# PEAWS.net
KiCad netlist of a schematic drawn in EAGLE
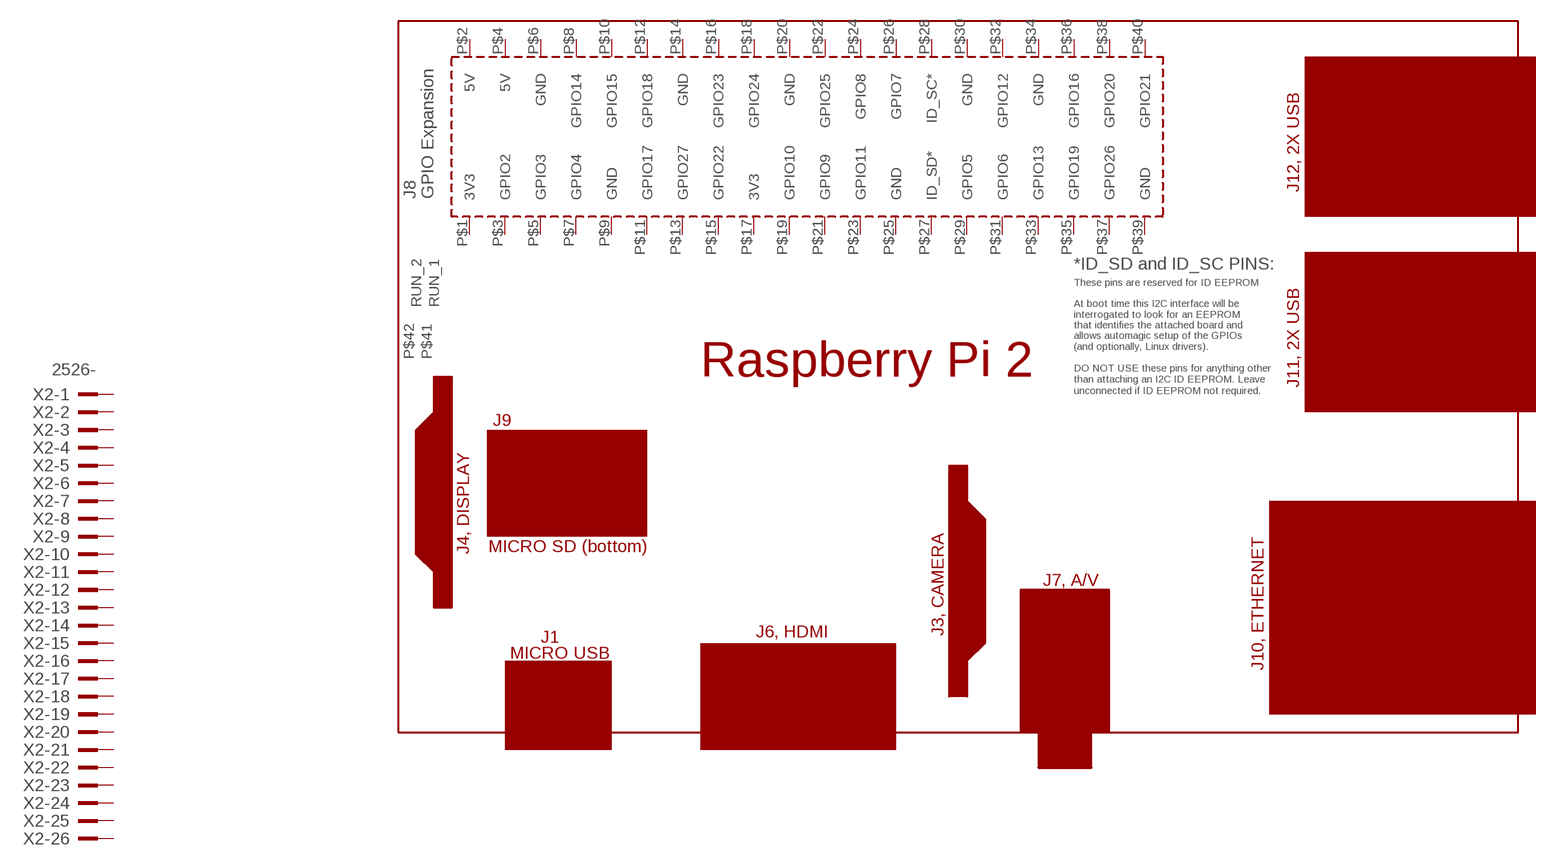
[diagram p0: schematic, sheet 1]
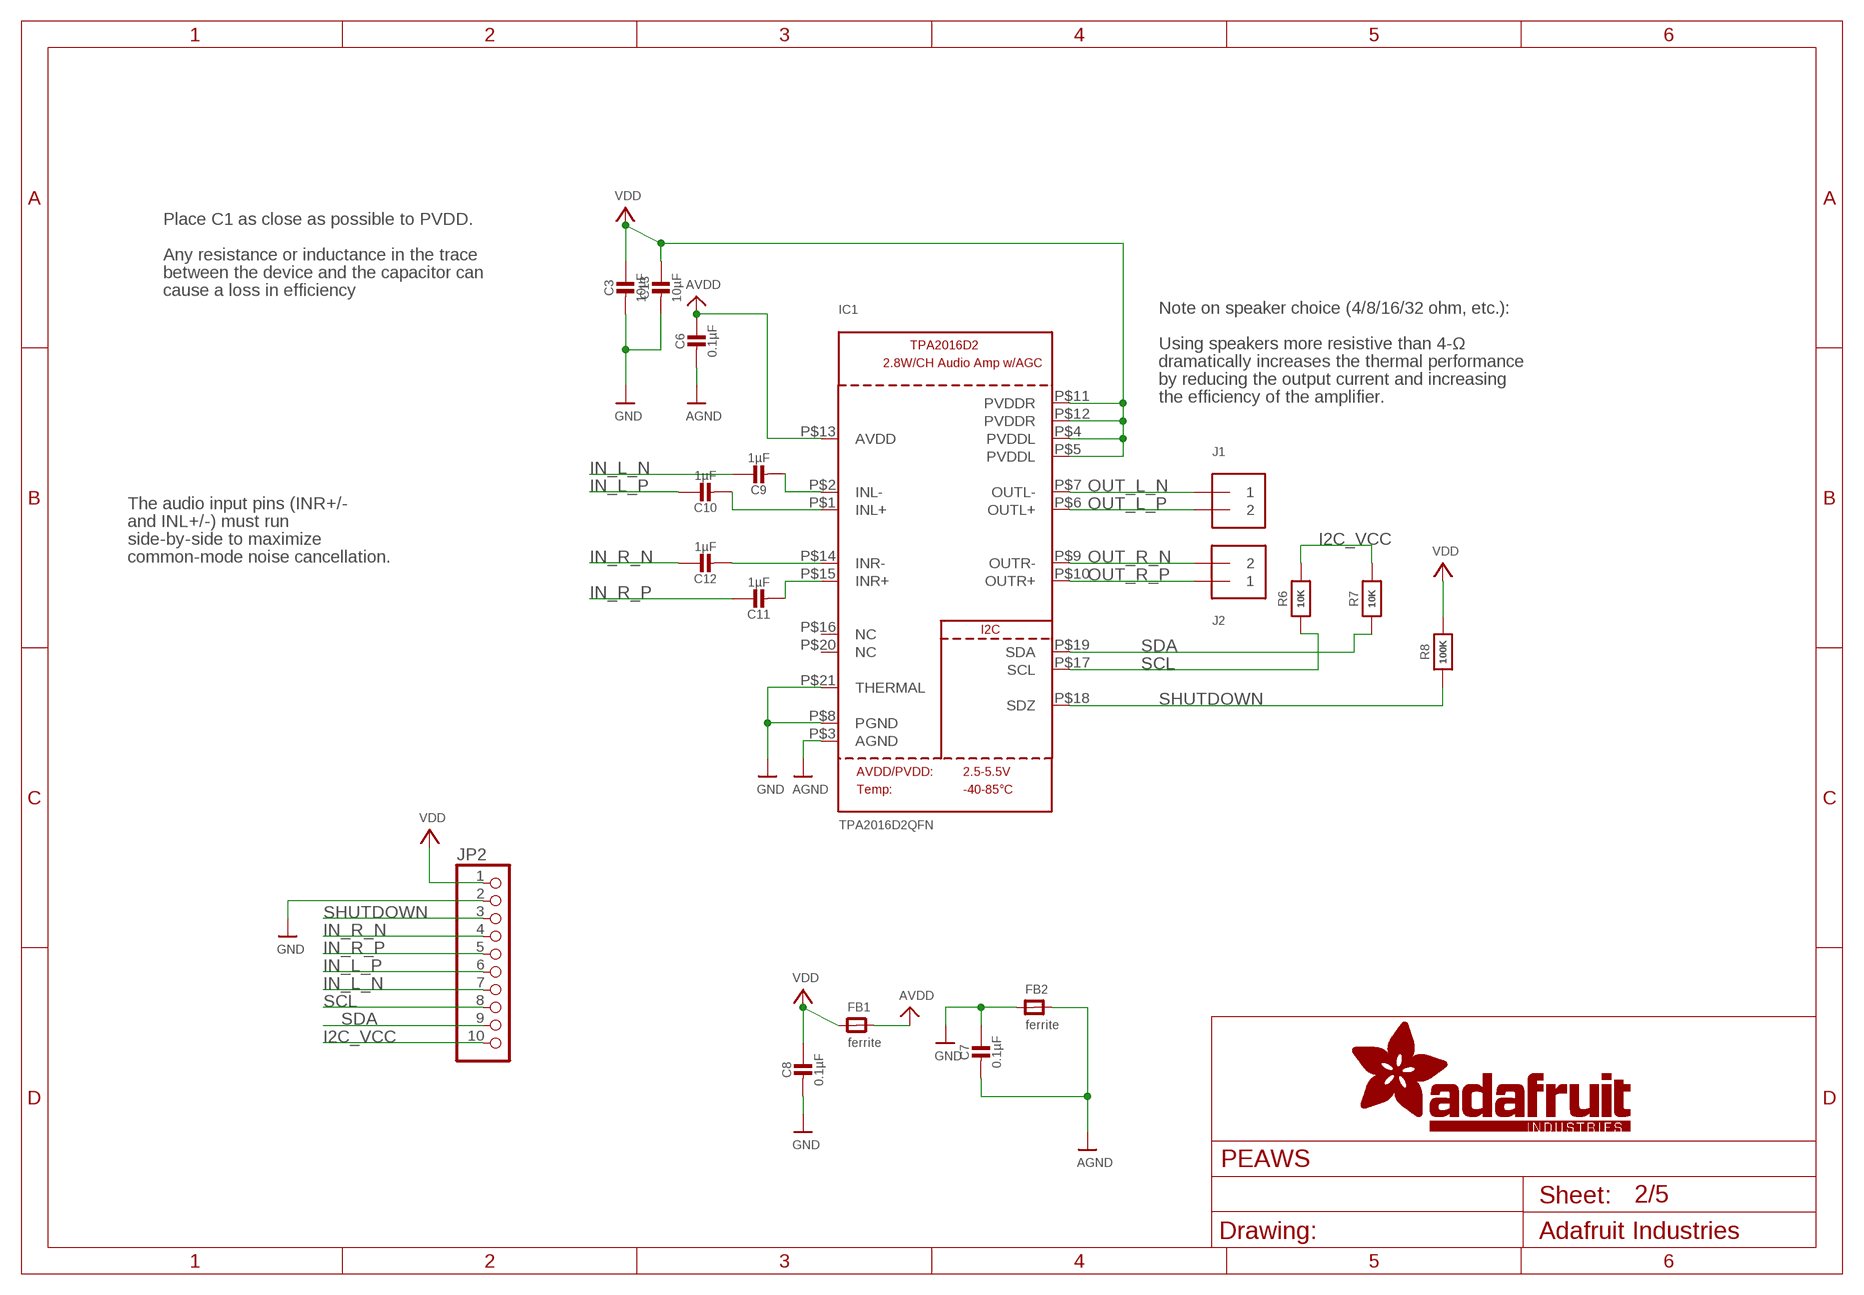
[diagram p1: schematic, sheet 2]
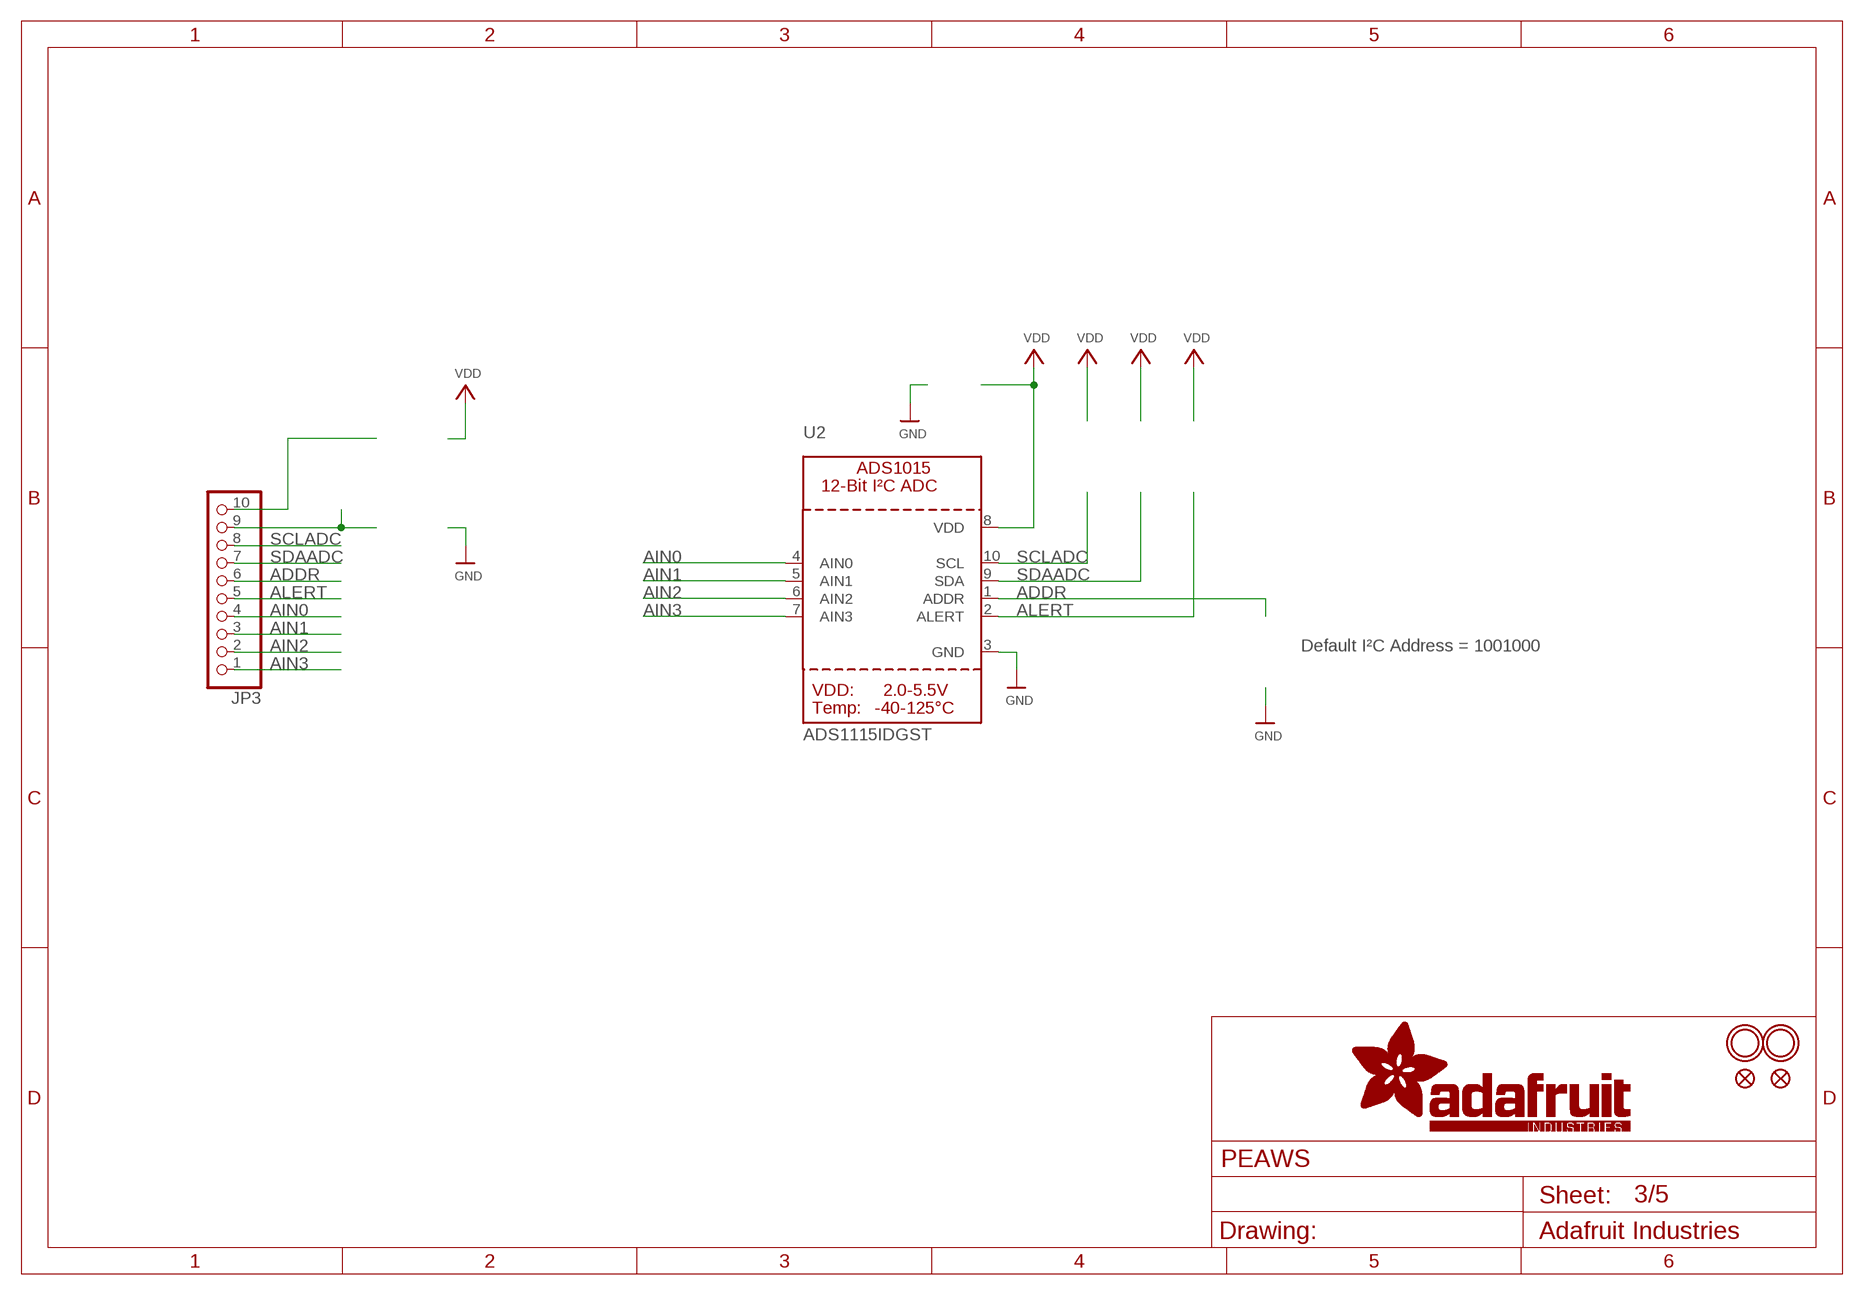
[diagram p2: schematic, sheet 3]
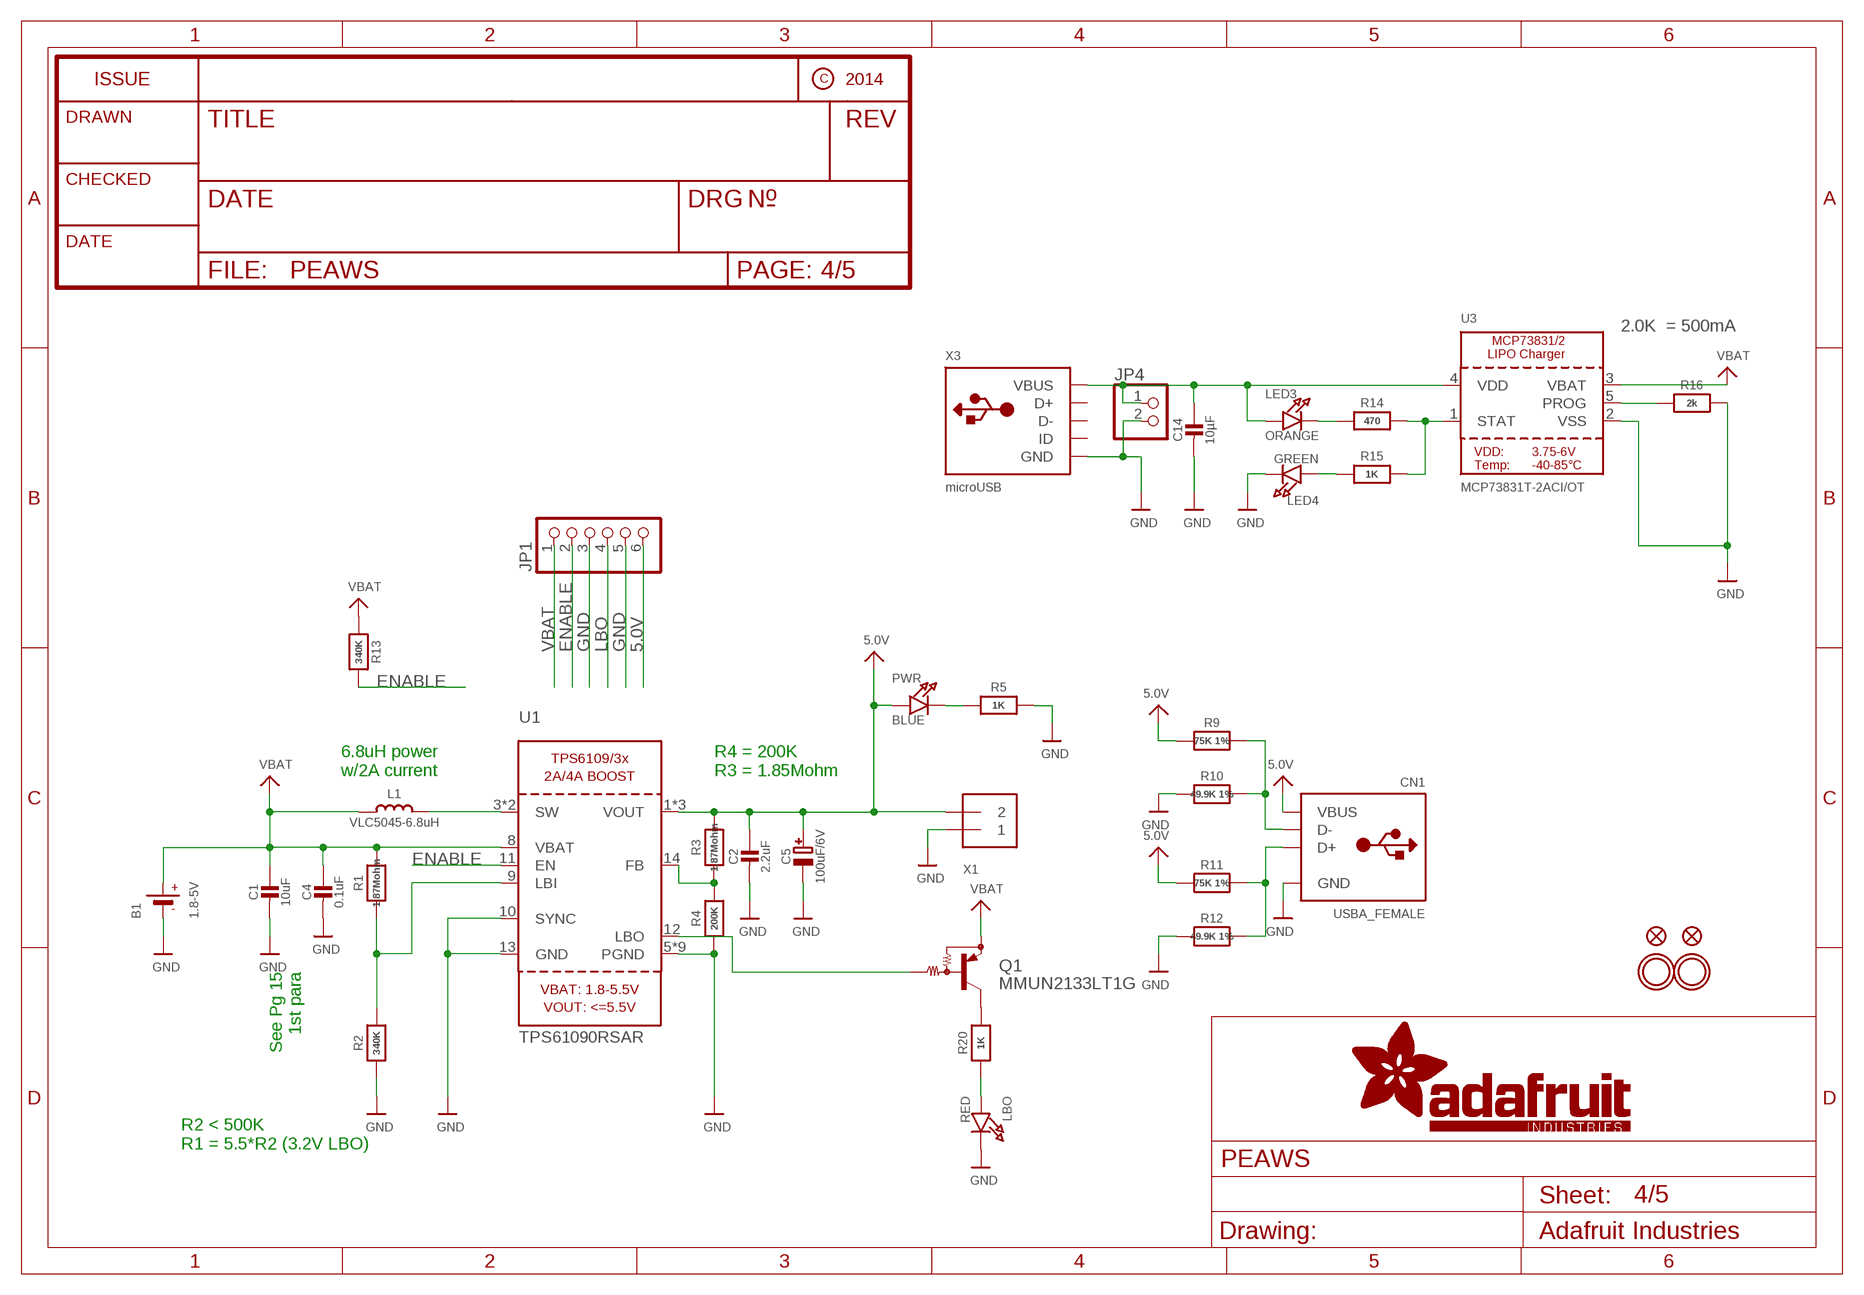
[diagram p3: schematic, sheet 4]
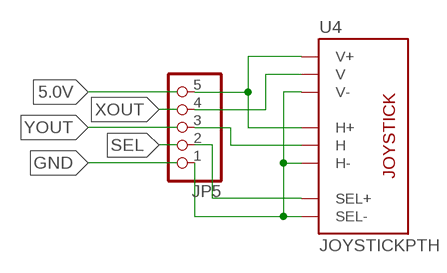
[diagram p4: schematic, sheet 5]

(export (version "E")
  (design (tool "Eeschema 10.0.6"))
  (components
    (comp (ref "C3")
      (value "10µF")
      (footprint "eagle-import:0805-NO")
      (libsource (lib "eagle-import") (part "CAP_CERAMIC0805-NOOUTLINE"))
    )
    (comp (ref "C6")
      (value "0.1µF")
      (footprint "eagle-import:0805-NO")
      (libsource (lib "eagle-import") (part "CAP_CERAMIC0805-NOOUTLINE"))
    )
    (comp (ref "C7")
      (value "0.1µF")
      (footprint "eagle-import:0805-NO")
      (libsource (lib "eagle-import") (part "CAP_CERAMIC0805-NOOUTLINE"))
    )
    (comp (ref "C8")
      (value "0.1µF")
      (footprint "eagle-import:0805-NO")
      (libsource (lib "eagle-import") (part "CAP_CERAMIC0805-NOOUTLINE"))
    )
    (comp (ref "C9")
      (value "1µF")
      (footprint "eagle-import:0805-NO")
      (libsource (lib "eagle-import") (part "CAP_CERAMIC0805-NOOUTLINE"))
    )
    (comp (ref "C10")
      (value "1µF")
      (footprint "eagle-import:0805-NO")
      (libsource (lib "eagle-import") (part "CAP_CERAMIC0805-NOOUTLINE"))
    )
    (comp (ref "C11")
      (value "1µF")
      (footprint "eagle-import:0805-NO")
      (libsource (lib "eagle-import") (part "CAP_CERAMIC0805-NOOUTLINE"))
    )
    (comp (ref "C12")
      (value "1µF")
      (footprint "eagle-import:0805-NO")
      (libsource (lib "eagle-import") (part "CAP_CERAMIC0805-NOOUTLINE"))
    )
    (comp (ref "C13")
      (value "10µF")
      (footprint "eagle-import:0805-NO")
      (libsource (lib "eagle-import") (part "CAP_CERAMIC0805-NOOUTLINE"))
    )
    (comp (ref "FB1")
      (value "ferrite")
      (footprint "eagle-import:_0805MP")
      (libsource (lib "eagle-import") (part "FERRITE_0805MP"))
    )
    (comp (ref "FB2")
      (value "ferrite")
      (footprint "eagle-import:_0805MP")
      (libsource (lib "eagle-import") (part "FERRITE_0805MP"))
    )
    (comp (ref "IC1")
      (value "TPA2016D2QFN")
      (footprint "eagle-import:QFN20_4MM")
      (libsource (lib "eagle-import") (part "TPA2016D2QFN"))
    )
    (comp (ref "J1")
      (value "TERMBLOCK_1X2")
      (footprint "eagle-import:TERMBLOCK_1X2-3.5MM")
      (libsource (lib "eagle-import") (part "TERMBLOCK_1X2"))
    )
    (comp (ref "J2")
      (value "TERMBLOCK_1X2")
      (footprint "eagle-import:TERMBLOCK_1X2-3.5MM")
      (libsource (lib "eagle-import") (part "TERMBLOCK_1X2"))
    )
    (comp (ref "JP2")
      (value "HEADER-1X1070MIL")
      (footprint "eagle-import:1X10_ROUND70")
      (libsource (lib "eagle-import") (part "HEADER-1X1070MIL"))
    )
    (comp (ref "R6")
      (value "10K")
      (footprint "eagle-import:0805-NO")
      (libsource (lib "eagle-import") (part "RESISTOR0805_NOOUTLINE"))
    )
    (comp (ref "R7")
      (value "10K")
      (footprint "eagle-import:0805-NO")
      (libsource (lib "eagle-import") (part "RESISTOR0805_NOOUTLINE"))
    )
    (comp (ref "R8")
      (value "100K")
      (footprint "eagle-import:0805-NO")
      (libsource (lib "eagle-import") (part "RESISTOR0805_NOOUTLINE"))
    )
    (comp (ref "PCB1")
      (value "RPI2")
      (footprint "eagle-import:RPI2")
      (libsource (lib "eagle-import") (part "RPI2"))
    )
    (comp (ref "X2")
      (value "2526-")
      (footprint "eagle-import:PAK100_2500-26")
      (libsource (lib "eagle-import") (part "2526-"))
    )
    (comp (ref "JP5")
      (value "PINHD-1X5")
      (footprint "eagle-import:1X05")
      (libsource (lib "eagle-import") (part "PINHD-1X5"))
    )
    (comp (ref "U4")
      (value "JOYSTICKPTH")
      (footprint "eagle-import:JOYSTICK")
      (libsource (lib "eagle-import") (part "JOYSTICKPTH"))
    )
    (comp (ref "FID1")
      (value "FIDUCIAL\"\"")
      (footprint "eagle-import:FIDUCIAL_1MM")
      (libsource (lib "eagle-import") (part "FIDUCIAL{dblquote}{dblquote}"))
    )
    (comp (ref "FID2")
      (value "FIDUCIAL\"\"")
      (footprint "eagle-import:FIDUCIAL_1MM")
      (libsource (lib "eagle-import") (part "FIDUCIAL{dblquote}{dblquote}"))
    )
    (comp (ref "JP3")
      (value "HEADER-1X1070MIL")
      (footprint "eagle-import:1X10_ROUND70")
      (libsource (lib "eagle-import") (part "HEADER-1X1070MIL"))
    )
    (comp (ref "U$55")
      (value "MOUNTINGHOLE2.5")
      (footprint "eagle-import:MOUNTINGHOLE_2.5_PLATED")
      (libsource (lib "eagle-import") (part "MOUNTINGHOLE2.5"))
    )
    (comp (ref "U$56")
      (value "MOUNTINGHOLE2.5")
      (footprint "eagle-import:MOUNTINGHOLE_2.5_PLATED")
      (libsource (lib "eagle-import") (part "MOUNTINGHOLE2.5"))
    )
    (comp (ref "U2")
      (value "ADS1115IDGST")
      (footprint "eagle-import:MSOP10")
      (libsource (lib "eagle-import") (part "ADC_ADS1015"))
    )
    (comp (ref "B1")
      (value "1.8-5V")
      (footprint "eagle-import:JSTPH2")
      (libsource (lib "eagle-import") (part "BATTERY"))
    )
    (comp (ref "C1")
      (value "10uF")
      (footprint "eagle-import:0805-NO")
      (libsource (lib "eagle-import") (part "CAP_CERAMIC0805-NOOUTLINE"))
    )
    (comp (ref "C2")
      (value "2.2uF")
      (footprint "eagle-import:0805-NO")
      (libsource (lib "eagle-import") (part "CAP_CERAMIC0805-NOOUTLINE"))
    )
    (comp (ref "C4")
      (value "0.1uF")
      (footprint "eagle-import:0805-NO")
      (libsource (lib "eagle-import") (part "CAP_CERAMIC0805-NOOUTLINE"))
    )
    (comp (ref "C5")
      (value "100uF/6V")
      (footprint "eagle-import:EIA3528-21_B-R")
      (libsource (lib "eagle-import") (part "CAP_TANTALUMB/3528_REFLOW"))
    )
    (comp (ref "C14")
      (value "10µF")
      (footprint "eagle-import:0805-NO")
      (libsource (lib "eagle-import") (part "CAP_CERAMIC0805-NOOUTLINE"))
    )
    (comp (ref "CN1")
      (value "USBA_FEMALE")
      (footprint "eagle-import:USB_HOST-PTH")
      (libsource (lib "eagle-import") (part "USB_TYPEAPTHFML"))
    )
    (comp (ref "FID3")
      (value "FIDUCIAL\"\"")
      (footprint "eagle-import:FIDUCIAL_1MM")
      (libsource (lib "eagle-import") (part "FIDUCIAL{dblquote}{dblquote}"))
    )
    (comp (ref "FID4")
      (value "FIDUCIAL\"\"")
      (footprint "eagle-import:FIDUCIAL_1MM")
      (fields (field (name "BOM") "EXCLUDE"))
      (libsource (lib "eagle-import") (part "FIDUCIAL{dblquote}{dblquote}"))
    )
    (comp (ref "JP1")
      (value "PINHD-1X6CB")
      (footprint "eagle-import:1X06-CLEANBIG")
      (libsource (lib "eagle-import") (part "PINHD-1X6CB"))
    )
    (comp (ref "JP4")
      (value "HEADER-1X2ROUND")
      (footprint "eagle-import:1X02_ROUND")
      (libsource (lib "eagle-import") (part "HEADER-1X2ROUND"))
    )
    (comp (ref "L1")
      (value "VLC5045-6.8uH")
      (footprint "eagle-import:INDUCTOR_5X5MM_TDK_VLC5045")
      (libsource (lib "eagle-import") (part "INDUCTORTDK_VLC5045"))
    )
    (comp (ref "LBO")
      (value "RED")
      (footprint "eagle-import:CHIPLED_0805_NOOUTLINE")
      (libsource (lib "eagle-import") (part "LED0805_NOOUTLINE"))
    )
    (comp (ref "LED3")
      (value "ORANGE")
      (footprint "eagle-import:CHIPLED_0805_NOOUTLINE")
      (libsource (lib "eagle-import") (part "LED0805_NOOUTLINE"))
    )
    (comp (ref "LED4")
      (value "GREEN")
      (footprint "eagle-import:CHIPLED_0805_NOOUTLINE")
      (libsource (lib "eagle-import") (part "LED0805_NOOUTLINE"))
    )
    (comp (ref "PWR")
      (value "BLUE")
      (footprint "eagle-import:CHIPLED_0805_NOOUTLINE")
      (libsource (lib "eagle-import") (part "LED0805_NOOUTLINE"))
    )
    (comp (ref "Q1")
      (value "MMUN2133LT1G")
      (footprint "eagle-import:SC59-BEC")
      (libsource (lib "eagle-import") (part "-PNP_DRIVER-SC59-BECMUN2114T1"))
    )
    (comp (ref "R1")
      (value "1.87Mohm")
      (footprint "eagle-import:0805-NO")
      (libsource (lib "eagle-import") (part "RESISTOR0805_NOOUTLINE"))
    )
    (comp (ref "R2")
      (value "340K")
      (footprint "eagle-import:0805-NO")
      (libsource (lib "eagle-import") (part "RESISTOR0805_NOOUTLINE"))
    )
    (comp (ref "R3")
      (value "1.87Mohm")
      (footprint "eagle-import:0805-NO")
      (libsource (lib "eagle-import") (part "RESISTOR0805_NOOUTLINE"))
    )
    (comp (ref "R4")
      (value "200K")
      (footprint "eagle-import:0805-NO")
      (libsource (lib "eagle-import") (part "RESISTOR0805_NOOUTLINE"))
    )
    (comp (ref "R5")
      (value "1K")
      (footprint "eagle-import:0805-NO")
      (libsource (lib "eagle-import") (part "RESISTOR0805_NOOUTLINE"))
    )
    (comp (ref "R9")
      (value "75K 1%")
      (footprint "eagle-import:0805-NO")
      (libsource (lib "eagle-import") (part "RESISTOR0805_NOOUTLINE"))
    )
    (comp (ref "R10")
      (value "49.9K 1%")
      (footprint "eagle-import:0805-NO")
      (libsource (lib "eagle-import") (part "RESISTOR0805_NOOUTLINE"))
    )
    (comp (ref "R11")
      (value "75K 1%")
      (footprint "eagle-import:0805-NO")
      (libsource (lib "eagle-import") (part "RESISTOR0805_NOOUTLINE"))
    )
    (comp (ref "R12")
      (value "49.9K 1%")
      (footprint "eagle-import:0805-NO")
      (libsource (lib "eagle-import") (part "RESISTOR0805_NOOUTLINE"))
    )
    (comp (ref "R13")
      (value "340K")
      (footprint "eagle-import:0805-NO")
      (libsource (lib "eagle-import") (part "RESISTOR0805_NOOUTLINE"))
    )
    (comp (ref "R14")
      (value "470")
      (footprint "eagle-import:0805-NO")
      (libsource (lib "eagle-import") (part "RESISTOR0805_NOOUTLINE"))
    )
    (comp (ref "R15")
      (value "1K")
      (footprint "eagle-import:0805-NO")
      (libsource (lib "eagle-import") (part "RESISTOR0805_NOOUTLINE"))
    )
    (comp (ref "R16")
      (value "2k")
      (footprint "eagle-import:0805-NO")
      (libsource (lib "eagle-import") (part "RESISTOR0805_NOOUTLINE"))
    )
    (comp (ref "R20")
      (value "1K")
      (footprint "eagle-import:0805-NO")
      (libsource (lib "eagle-import") (part "RESISTOR0805_NOOUTLINE"))
    )
    (comp (ref "U$3")
      (value "MOUNTINGHOLE2.5")
      (footprint "eagle-import:MOUNTINGHOLE_2.5_PLATED")
      (libsource (lib "eagle-import") (part "MOUNTINGHOLE2.5"))
    )
    (comp (ref "U$6")
      (value "MOUNTINGHOLE2.5")
      (footprint "eagle-import:MOUNTINGHOLE_2.5_PLATED")
      (libsource (lib "eagle-import") (part "MOUNTINGHOLE2.5"))
    )
    (comp (ref "U1")
      (value "TPS61090RSAR")
      (footprint "eagle-import:PVQFN-16")
      (libsource (lib "eagle-import") (part "VREG_TPS6103X"))
    )
    (comp (ref "U3")
      (value "MCP73831T-2ACI/OT")
      (footprint "eagle-import:SOT23-5")
      (libsource (lib "eagle-import") (part "MCP73831/2"))
    )
    (comp (ref "X1")
      (value "TERMBLOCK_1X2")
      (footprint "eagle-import:TERMBLOCK_1X2-3.5MM")
      (libsource (lib "eagle-import") (part "TERMBLOCK_1X2"))
    )
    (comp (ref "X3")
      (value "microUSB")
      (footprint "eagle-import:4UCONN_20329")
      (libsource (lib "eagle-import") (part "USBMICRO_20329"))
    )
  )
  (nets
    (net (code "1") (name "5.0V") (class "Default")
      (node (ref "C2") (pin "1") (pinfunction "1_1") (pintype "passive"))
      (node (ref "C5") (pin "+") (pinfunction "+_+") (pintype "passive"))
      (node (ref "CN1") (pin "VBUS") (pinfunction "VBUS_VBUS") (pintype "power_in"))
      (node (ref "JP1") (pin "6") (pinfunction "6_6") (pintype "passive"))
      (node (ref "PWR") (pin "A") (pinfunction "A_A") (pintype "passive"))
      (node (ref "R11") (pin "2") (pinfunction "2_2") (pintype "passive"))
      (node (ref "R3") (pin "2") (pinfunction "2_2") (pintype "passive"))
      (node (ref "R9") (pin "2") (pinfunction "2_2") (pintype "passive"))
      (node (ref "U1") (pin "1") (pinfunction "VOUT_1") (pintype "power_in"))
      (node (ref "U1") (pin "15") (pinfunction "VOUT_15") (pintype "power_in"))
      (node (ref "U1") (pin "16") (pinfunction "VOUT_16") (pintype "power_in"))
      (node (ref "X1") (pin "2") (pinfunction "2_2") (pintype "passive"))
    )
    (net (code "2") (name "ADDR") (class "Default")
      (node (ref "JP3") (pin "6") (pinfunction "6_6") (pintype "passive"))
      (node (ref "U2") (pin "1") (pinfunction "ADDR_1") (pintype "bidirectional"))
    )
    (net (code "3") (name "AGND") (class "Default")
      (node (ref "C6") (pin "2") (pinfunction "2_2") (pintype "passive"))
      (node (ref "C7") (pin "2") (pinfunction "2_2") (pintype "passive"))
      (node (ref "FB2") (pin "2") (pinfunction "P$2_2") (pintype "passive"))
      (node (ref "IC1") (pin "P$3") (pinfunction "AGND_P$3") (pintype "power_in"))
    )
    (net (code "4") (name "AIN0") (class "Default")
      (node (ref "JP3") (pin "4") (pinfunction "4_4") (pintype "passive"))
      (node (ref "U2") (pin "4") (pinfunction "AIN0_4") (pintype "bidirectional"))
    )
    (net (code "5") (name "AIN1") (class "Default")
      (node (ref "JP3") (pin "3") (pinfunction "3_3") (pintype "passive"))
      (node (ref "U2") (pin "5") (pinfunction "AIN1_5") (pintype "bidirectional"))
    )
    (net (code "6") (name "AIN2") (class "Default")
      (node (ref "JP3") (pin "2") (pinfunction "2_2") (pintype "passive"))
      (node (ref "U2") (pin "6") (pinfunction "AIN2_6") (pintype "bidirectional"))
    )
    (net (code "7") (name "AIN3") (class "Default")
      (node (ref "JP3") (pin "1") (pinfunction "1_1") (pintype "passive"))
      (node (ref "U2") (pin "7") (pinfunction "AIN3_7") (pintype "bidirectional"))
    )
    (net (code "8") (name "ALERT") (class "Default")
      (node (ref "JP3") (pin "5") (pinfunction "5_5") (pintype "passive"))
      (node (ref "U2") (pin "2") (pinfunction "ALERT_2") (pintype "bidirectional"))
    )
    (net (code "9") (name "AVDD") (class "Default")
      (node (ref "C6") (pin "1") (pinfunction "1_1") (pintype "passive"))
      (node (ref "FB1") (pin "2") (pinfunction "P$2_2") (pintype "passive"))
      (node (ref "IC1") (pin "P$13") (pinfunction "AVDD_P$13") (pintype "power_in"))
    )
    (net (code "10") (name "ENABLE") (class "Default")
      (node (ref "JP1") (pin "2") (pinfunction "2_2") (pintype "passive"))
      (node (ref "R13") (pin "2") (pinfunction "2_2") (pintype "passive"))
      (node (ref "U1") (pin "11") (pinfunction "EN_11") (pintype "input"))
    )
    (net (code "11") (name "GND") (class "Default")
      (node (ref "B1") (pin "1") (pinfunction "-_1") (pintype "passive"))
      (node (ref "C1") (pin "2") (pinfunction "2_2") (pintype "passive"))
      (node (ref "C13") (pin "2") (pinfunction "2_2") (pintype "passive"))
      (node (ref "C14") (pin "2") (pinfunction "2_2") (pintype "passive"))
      (node (ref "C2") (pin "2") (pinfunction "2_2") (pintype "passive"))
      (node (ref "C3") (pin "2") (pinfunction "2_2") (pintype "passive"))
      (node (ref "C4") (pin "2") (pinfunction "2_2") (pintype "passive"))
      (node (ref "C5") (pin "-") (pinfunction "-_-") (pintype "passive"))
      (node (ref "C7") (pin "1") (pinfunction "1_1") (pintype "passive"))
      (node (ref "C8") (pin "2") (pinfunction "2_2") (pintype "passive"))
      (node (ref "CN1") (pin "GND") (pinfunction "GND_GND") (pintype "power_in"))
      (node (ref "FB2") (pin "1") (pinfunction "P$1_1") (pintype "passive"))
      (node (ref "IC1") (pin "P$21") (pinfunction "THERMAL_P$21") (pintype "bidirectional"))
      (node (ref "IC1") (pin "P$8") (pinfunction "PGND_P$8") (pintype "power_in"))
      (node (ref "JP1") (pin "3") (pinfunction "3_3") (pintype "passive"))
      (node (ref "JP1") (pin "5") (pinfunction "5_5") (pintype "passive"))
      (node (ref "JP2") (pin "2") (pinfunction "2_2") (pintype "passive"))
      (node (ref "JP4") (pin "2") (pinfunction "2_2") (pintype "passive"))
      (node (ref "LBO") (pin "C") (pinfunction "C_C") (pintype "passive"))
      (node (ref "LED4") (pin "C") (pinfunction "C_C") (pintype "passive"))
      (node (ref "R10") (pin "2") (pinfunction "2_2") (pintype "passive"))
      (node (ref "R12") (pin "2") (pinfunction "2_2") (pintype "passive"))
      (node (ref "R16") (pin "2") (pinfunction "2_2") (pintype "passive"))
      (node (ref "R2") (pin "1") (pinfunction "1_1") (pintype "passive"))
      (node (ref "R4") (pin "1") (pinfunction "1_1") (pintype "passive"))
      (node (ref "R5") (pin "2") (pinfunction "2_2") (pintype "passive"))
      (node (ref "U1") (pin "10") (pinfunction "SYNC_10") (pintype "input"))
      (node (ref "U1") (pin "13") (pinfunction "GND_13") (pintype "power_in"))
      (node (ref "U1") (pin "5") (pinfunction "PGND_5") (pintype "power_in"))
      (node (ref "U1") (pin "6") (pinfunction "PGND_6") (pintype "power_in"))
      (node (ref "U1") (pin "7") (pinfunction "PGND_7") (pintype "power_in"))
      (node (ref "U1") (pin "P$18") (pinfunction "PGND_P$18") (pintype "power_in"))
      (node (ref "U1") (pin "P$19") (pinfunction "PGND_P$19") (pintype "power_in"))
      (node (ref "U1") (pin "P$20") (pinfunction "PGND_P$20") (pintype "power_in"))
      (node (ref "U1") (pin "P$21") (pinfunction "PGND_P$21") (pintype "power_in"))
      (node (ref "U1") (pin "P$22") (pinfunction "PGND_P$22") (pintype "power_in"))
      (node (ref "U1") (pin "THERMAL") (pinfunction "PGND_THERMAL") (pintype "power_in"))
      (node (ref "U2") (pin "3") (pinfunction "GND_3") (pintype "bidirectional"))
      (node (ref "U3") (pin "2") (pinfunction "VSS_2") (pintype "power_in"))
      (node (ref "X1") (pin "1") (pinfunction "1_1") (pintype "passive"))
      (node (ref "X3") (pin "BASE@1") (pinfunction "GND_BASE@1") (pintype "power_in"))
      (node (ref "X3") (pin "BASE@2") (pinfunction "GND_BASE@2") (pintype "power_in"))
      (node (ref "X3") (pin "GND") (pinfunction "GND_GND") (pintype "power_in"))
      (node (ref "X3") (pin "SPRT@1") (pinfunction "GND_SPRT@1") (pintype "power_in"))
      (node (ref "X3") (pin "SPRT@2") (pinfunction "GND_SPRT@2") (pintype "power_in"))
      (node (ref "X3") (pin "SPRT@3") (pinfunction "GND_SPRT@3") (pintype "power_in"))
      (node (ref "X3") (pin "SPRT@4") (pinfunction "GND_SPRT@4") (pintype "power_in"))
    )
    (net (code "12") (name "I2C_VCC") (class "Default")
      (node (ref "JP2") (pin "10") (pinfunction "10_10") (pintype "passive"))
      (node (ref "R6") (pin "2") (pinfunction "2_2") (pintype "passive"))
      (node (ref "R7") (pin "2") (pinfunction "2_2") (pintype "passive"))
    )
    (net (code "13") (name "IN_L_N") (class "Default")
      (node (ref "C9") (pin "1") (pinfunction "1_1") (pintype "passive"))
      (node (ref "JP2") (pin "7") (pinfunction "7_7") (pintype "passive"))
    )
    (net (code "14") (name "IN_L_P") (class "Default")
      (node (ref "C10") (pin "1") (pinfunction "1_1") (pintype "passive"))
      (node (ref "JP2") (pin "6") (pinfunction "6_6") (pintype "passive"))
    )
    (net (code "15") (name "IN_R_N") (class "Default")
      (node (ref "C12") (pin "1") (pinfunction "1_1") (pintype "passive"))
      (node (ref "JP2") (pin "4") (pinfunction "4_4") (pintype "passive"))
    )
    (net (code "16") (name "IN_R_P") (class "Default")
      (node (ref "C11") (pin "1") (pinfunction "1_1") (pintype "passive"))
      (node (ref "JP2") (pin "5") (pinfunction "5_5") (pintype "passive"))
    )
    (net (code "17") (name "LBO") (class "Default")
      (node (ref "JP1") (pin "4") (pinfunction "4_4") (pintype "passive"))
      (node (ref "Q1") (pin "B") (pinfunction "B_B") (pintype "passive"))
      (node (ref "U1") (pin "12") (pinfunction "LBO_12") (pintype "output"))
    )
    (net (code "18") (name "Net-(CN1-PadD+)") (class "Default")
      (node (ref "CN1") (pin "D+") (pinfunction "D+_D+") (pintype "bidirectional"))
      (node (ref "R11") (pin "1") (pinfunction "1_1") (pintype "passive"))
      (node (ref "R12") (pin "1") (pinfunction "1_1") (pintype "passive"))
    )
    (net (code "19") (name "Net-(CN1-PadD-)") (class "Default")
      (node (ref "CN1") (pin "D-") (pinfunction "D-_D-") (pintype "bidirectional"))
      (node (ref "R10") (pin "1") (pinfunction "1_1") (pintype "passive"))
      (node (ref "R9") (pin "1") (pinfunction "1_1") (pintype "passive"))
    )
    (net (code "20") (name "Net-(IC1-INL+)") (class "Default")
      (node (ref "C10") (pin "2") (pinfunction "2_2") (pintype "passive"))
      (node (ref "IC1") (pin "P$1") (pinfunction "INL+_P$1") (pintype "input"))
    )
    (net (code "21") (name "Net-(IC1-INL-)") (class "Default")
      (node (ref "C9") (pin "2") (pinfunction "2_2") (pintype "passive"))
      (node (ref "IC1") (pin "P$2") (pinfunction "INL-_P$2") (pintype "input"))
    )
    (net (code "22") (name "Net-(IC1-INR+)") (class "Default")
      (node (ref "C11") (pin "2") (pinfunction "2_2") (pintype "passive"))
      (node (ref "IC1") (pin "P$15") (pinfunction "INR+_P$15") (pintype "input"))
    )
    (net (code "23") (name "Net-(IC1-INR-)") (class "Default")
      (node (ref "C12") (pin "2") (pinfunction "2_2") (pintype "passive"))
      (node (ref "IC1") (pin "P$14") (pinfunction "INR-_P$14") (pintype "input"))
    )
    (net (code "24") (name "Net-(L1-2)") (class "Default")
      (node (ref "L1") (pin "P$2") (pinfunction "2_P$2") (pintype "passive"))
      (node (ref "U1") (pin "3") (pinfunction "SW_3") (pintype "input"))
      (node (ref "U1") (pin "4") (pinfunction "SW_4") (pintype "input"))
    )
    (net (code "25") (name "Net-(LBO-PadA)") (class "Default")
      (node (ref "LBO") (pin "A") (pinfunction "A_A") (pintype "passive"))
      (node (ref "R20") (pin "1") (pinfunction "1_1") (pintype "passive"))
    )
    (net (code "26") (name "Net-(LED3-PadC)") (class "Default")
      (node (ref "LED3") (pin "C") (pinfunction "C_C") (pintype "passive"))
      (node (ref "R14") (pin "1") (pinfunction "1_1") (pintype "passive"))
    )
    (net (code "27") (name "Net-(LED4-PadA)") (class "Default")
      (node (ref "LED4") (pin "A") (pinfunction "A_A") (pintype "passive"))
      (node (ref "R15") (pin "1") (pinfunction "1_1") (pintype "passive"))
    )
    (net (code "28") (name "Net-(PWR-PadC)") (class "Default")
      (node (ref "PWR") (pin "C") (pinfunction "C_C") (pintype "passive"))
      (node (ref "R5") (pin "1") (pinfunction "1_1") (pintype "passive"))
    )
    (net (code "29") (name "Net-(Q1-PadC)") (class "Default")
      (node (ref "Q1") (pin "C") (pinfunction "C_C") (pintype "passive"))
      (node (ref "R20") (pin "2") (pinfunction "2_2") (pintype "passive"))
    )
    (net (code "30") (name "Net-(U1-FB)") (class "Default")
      (node (ref "R3") (pin "1") (pinfunction "1_1") (pintype "passive"))
      (node (ref "R4") (pin "2") (pinfunction "2_2") (pintype "passive"))
      (node (ref "U1") (pin "14") (pinfunction "FB_14") (pintype "input"))
    )
    (net (code "31") (name "Net-(U1-LBI)") (class "Default")
      (node (ref "R1") (pin "1") (pinfunction "1_1") (pintype "passive"))
      (node (ref "R2") (pin "2") (pinfunction "2_2") (pintype "passive"))
      (node (ref "U1") (pin "9") (pinfunction "LBI_9") (pintype "input"))
    )
    (net (code "32") (name "Net-(U3-PROG)") (class "Default")
      (node (ref "R16") (pin "1") (pinfunction "1_1") (pintype "passive"))
      (node (ref "U3") (pin "5") (pinfunction "PROG_5") (pintype "input"))
    )
    (net (code "33") (name "Net-(U3-STAT)") (class "Default")
      (node (ref "R14") (pin "2") (pinfunction "2_2") (pintype "passive"))
      (node (ref "R15") (pin "2") (pinfunction "2_2") (pintype "passive"))
      (node (ref "U3") (pin "1") (pinfunction "STAT_1") (pintype "output"))
    )
    (net (code "34") (name "Net-(U3-VDD)") (class "Default")
      (node (ref "C14") (pin "1") (pinfunction "1_1") (pintype "passive"))
      (node (ref "JP4") (pin "1") (pinfunction "1_1") (pintype "passive"))
      (node (ref "LED3") (pin "A") (pinfunction "A_A") (pintype "passive"))
      (node (ref "U3") (pin "4") (pinfunction "VDD_4") (pintype "power_in"))
      (node (ref "X3") (pin "VBUS") (pinfunction "VBUS_VBUS") (pintype "power_in"))
    )
    (net (code "35") (name "Net-(U4-H)") (class "Default")
      (node (ref "JP5") (pin "3") (pinfunction "3_3") (pintype "passive"))
      (node (ref "U4") (pin "H2") (pinfunction "H_H2") (pintype "bidirectional"))
    )
    (net (code "36") (name "Net-(U4-H+)") (class "Default")
      (node (ref "JP5") (pin "5") (pinfunction "5_5") (pintype "passive"))
      (node (ref "U4") (pin "H1") (pinfunction "H+_H1") (pintype "bidirectional"))
      (node (ref "U4") (pin "V1") (pinfunction "V+_V1") (pintype "bidirectional"))
    )
    (net (code "37") (name "Net-(U4-H-)") (class "Default")
      (node (ref "JP5") (pin "1") (pinfunction "1_1") (pintype "passive"))
      (node (ref "U4") (pin "B2A") (pinfunction "SEL-_B2A") (pintype "bidirectional"))
      (node (ref "U4") (pin "H3") (pinfunction "H-_H3") (pintype "bidirectional"))
      (node (ref "U4") (pin "V3") (pinfunction "V-_V3") (pintype "bidirectional"))
    )
    (net (code "38") (name "Net-(U4-SEL+)") (class "Default")
      (node (ref "JP5") (pin "2") (pinfunction "2_2") (pintype "passive"))
      (node (ref "U4") (pin "B1A") (pinfunction "SEL+_B1A") (pintype "bidirectional"))
    )
    (net (code "39") (name "Net-(U4-V)") (class "Default")
      (node (ref "JP5") (pin "4") (pinfunction "4_4") (pintype "passive"))
      (node (ref "U4") (pin "V2") (pinfunction "V_V2") (pintype "bidirectional"))
    )
    (net (code "40") (name "OUT_L_N") (class "Default")
      (node (ref "IC1") (pin "P$7") (pinfunction "OUTL-_P$7") (pintype "output"))
      (node (ref "J1") (pin "1") (pinfunction "1_1") (pintype "passive"))
    )
    (net (code "41") (name "OUT_L_P") (class "Default")
      (node (ref "IC1") (pin "P$6") (pinfunction "OUTL+_P$6") (pintype "output"))
      (node (ref "J1") (pin "2") (pinfunction "2_2") (pintype "passive"))
    )
    (net (code "42") (name "OUT_R_N") (class "Default")
      (node (ref "IC1") (pin "P$9") (pinfunction "OUTR-_P$9") (pintype "output"))
      (node (ref "J2") (pin "2") (pinfunction "2_2") (pintype "passive"))
    )
    (net (code "43") (name "OUT_R_P") (class "Default")
      (node (ref "IC1") (pin "P$10") (pinfunction "OUTR+_P$10") (pintype "output"))
      (node (ref "J2") (pin "1") (pinfunction "1_1") (pintype "passive"))
    )
    (net (code "44") (name "SCL") (class "Default")
      (node (ref "IC1") (pin "P$17") (pinfunction "SCL_P$17") (pintype "bidirectional"))
      (node (ref "JP2") (pin "8") (pinfunction "8_8") (pintype "passive"))
      (node (ref "R6") (pin "1") (pinfunction "1_1") (pintype "passive"))
    )
    (net (code "45") (name "SCLADC") (class "Default")
      (node (ref "JP3") (pin "8") (pinfunction "8_8") (pintype "passive"))
      (node (ref "U2") (pin "10") (pinfunction "SCL_10") (pintype "bidirectional"))
    )
    (net (code "46") (name "SDA") (class "Default")
      (node (ref "IC1") (pin "P$19") (pinfunction "SDA_P$19") (pintype "bidirectional"))
      (node (ref "JP2") (pin "9") (pinfunction "9_9") (pintype "passive"))
      (node (ref "R7") (pin "1") (pinfunction "1_1") (pintype "passive"))
    )
    (net (code "47") (name "SDAADC") (class "Default")
      (node (ref "JP3") (pin "7") (pinfunction "7_7") (pintype "passive"))
      (node (ref "U2") (pin "9") (pinfunction "SDA_9") (pintype "bidirectional"))
    )
    (net (code "49") (name "SHUTDOWN") (class "Default")
      (node (ref "IC1") (pin "P$18") (pinfunction "SDZ_P$18") (pintype "input"))
      (node (ref "JP2") (pin "3") (pinfunction "3_3") (pintype "passive"))
      (node (ref "R8") (pin "1") (pinfunction "1_1") (pintype "passive"))
    )
    (net (code "50") (name "VBAT") (class "Default")
      (node (ref "B1") (pin "2") (pinfunction "+_2") (pintype "passive"))
      (node (ref "C1") (pin "1") (pinfunction "1_1") (pintype "passive"))
      (node (ref "C4") (pin "1") (pinfunction "1_1") (pintype "passive"))
      (node (ref "JP1") (pin "1") (pinfunction "1_1") (pintype "passive"))
      (node (ref "L1") (pin "P$1") (pinfunction "1_P$1") (pintype "passive"))
      (node (ref "Q1") (pin "E") (pinfunction "E_E") (pintype "passive"))
      (node (ref "R1") (pin "2") (pinfunction "2_2") (pintype "passive"))
      (node (ref "R13") (pin "1") (pinfunction "1_1") (pintype "passive"))
      (node (ref "U1") (pin "8") (pinfunction "VBAT_8") (pintype "input"))
      (node (ref "U3") (pin "3") (pinfunction "VBAT_3") (pintype "power_in"))
    )
    (net (code "51") (name "VDD") (class "Default")
      (node (ref "C13") (pin "1") (pinfunction "1_1") (pintype "passive"))
      (node (ref "C3") (pin "1") (pinfunction "1_1") (pintype "passive"))
      (node (ref "C8") (pin "1") (pinfunction "1_1") (pintype "passive"))
      (node (ref "FB1") (pin "1") (pinfunction "P$1_1") (pintype "passive"))
      (node (ref "IC1") (pin "P$11") (pinfunction "PVDDR_P$11") (pintype "power_in"))
      (node (ref "IC1") (pin "P$12") (pinfunction "PVDDR_P$12") (pintype "power_in"))
      (node (ref "IC1") (pin "P$4") (pinfunction "PVDDL_P$4") (pintype "power_in"))
      (node (ref "IC1") (pin "P$5") (pinfunction "PVDDL_P$5") (pintype "power_in"))
      (node (ref "JP2") (pin "1") (pinfunction "1_1") (pintype "passive"))
      (node (ref "R8") (pin "2") (pinfunction "2_2") (pintype "passive"))
      (node (ref "U2") (pin "8") (pinfunction "VDD_8") (pintype "bidirectional"))
    )
    (net (code "54") (name "unconnected-(IC1-NC-PadP$16)") (class "Default")
      (node (ref "IC1") (pin "P$16") (pinfunction "NC_P$16") (pintype "no_connect"))
    )
    (net (code "55") (name "unconnected-(IC1-NC-PadP$20)") (class "Default")
      (node (ref "IC1") (pin "P$20") (pinfunction "NC_P$20") (pintype "no_connect"))
    )
    (net (code "56") (name "unconnected-(JP3-Pad9)") (class "Default")
      (node (ref "JP3") (pin "9") (pinfunction "9_9") (pintype "passive"))
    )
    (net (code "57") (name "unconnected-(JP3-Pad10)") (class "Default")
      (node (ref "JP3") (pin "10") (pinfunction "10_10") (pintype "passive"))
    )
    (net (code "58") (name "unconnected-(PCB1-3V3-PadP$1)") (class "Default")
      (node (ref "PCB1") (pin "P$1") (pinfunction "3V3_P$1") (pintype "bidirectional"))
    )
    (net (code "59") (name "unconnected-(PCB1-3V3-PadP$17)") (class "Default")
      (node (ref "PCB1") (pin "P$17") (pinfunction "3V3_P$17") (pintype "bidirectional"))
    )
    (net (code "60") (name "unconnected-(PCB1-5V-PadP$2)") (class "Default")
      (node (ref "PCB1") (pin "P$2") (pinfunction "5V_P$2") (pintype "bidirectional"))
    )
    (net (code "61") (name "unconnected-(PCB1-5V-PadP$4)") (class "Default")
      (node (ref "PCB1") (pin "P$4") (pinfunction "5V_P$4") (pintype "bidirectional"))
    )
    (net (code "62") (name "unconnected-(PCB1-GND-PadP$6)") (class "Default")
      (node (ref "PCB1") (pin "P$6") (pinfunction "GND_P$6") (pintype "bidirectional"))
    )
    (net (code "63") (name "unconnected-(PCB1-GND-PadP$9)") (class "Default")
      (node (ref "PCB1") (pin "P$9") (pinfunction "GND_P$9") (pintype "bidirectional"))
    )
    (net (code "64") (name "unconnected-(PCB1-GND-PadP$14)") (class "Default")
      (node (ref "PCB1") (pin "P$14") (pinfunction "GND_P$14") (pintype "bidirectional"))
    )
    (net (code "65") (name "unconnected-(PCB1-GND-PadP$20)") (class "Default")
      (node (ref "PCB1") (pin "P$20") (pinfunction "GND_P$20") (pintype "bidirectional"))
    )
    (net (code "66") (name "unconnected-(PCB1-GND-PadP$25)") (class "Default")
      (node (ref "PCB1") (pin "P$25") (pinfunction "GND_P$25") (pintype "bidirectional"))
    )
    (net (code "67") (name "unconnected-(PCB1-GND-PadP$30)") (class "Default")
      (node (ref "PCB1") (pin "P$30") (pinfunction "GND_P$30") (pintype "bidirectional"))
    )
    (net (code "68") (name "unconnected-(PCB1-GND-PadP$34)") (class "Default")
      (node (ref "PCB1") (pin "P$34") (pinfunction "GND_P$34") (pintype "bidirectional"))
    )
    (net (code "69") (name "unconnected-(PCB1-GND-PadP$39)") (class "Default")
      (node (ref "PCB1") (pin "P$39") (pinfunction "GND_P$39") (pintype "bidirectional"))
    )
    (net (code "70") (name "unconnected-(PCB1-GPIO2-PadP$3)") (class "Default")
      (node (ref "PCB1") (pin "P$3") (pinfunction "GPIO2_P$3") (pintype "bidirectional"))
    )
    (net (code "71") (name "unconnected-(PCB1-GPIO3-PadP$5)") (class "Default")
      (node (ref "PCB1") (pin "P$5") (pinfunction "GPIO3_P$5") (pintype "bidirectional"))
    )
    (net (code "72") (name "unconnected-(PCB1-GPIO4-PadP$7)") (class "Default")
      (node (ref "PCB1") (pin "P$7") (pinfunction "GPIO4_P$7") (pintype "bidirectional"))
    )
    (net (code "73") (name "unconnected-(PCB1-GPIO5-PadP$29)") (class "Default")
      (node (ref "PCB1") (pin "P$29") (pinfunction "GPIO5_P$29") (pintype "bidirectional"))
    )
    (net (code "74") (name "unconnected-(PCB1-GPIO6-PadP$31)") (class "Default")
      (node (ref "PCB1") (pin "P$31") (pinfunction "GPIO6_P$31") (pintype "bidirectional"))
    )
    (net (code "75") (name "unconnected-(PCB1-GPIO7-PadP$26)") (class "Default")
      (node (ref "PCB1") (pin "P$26") (pinfunction "GPIO7_P$26") (pintype "bidirectional"))
    )
    (net (code "76") (name "unconnected-(PCB1-GPIO8-PadP$24)") (class "Default")
      (node (ref "PCB1") (pin "P$24") (pinfunction "GPIO8_P$24") (pintype "bidirectional"))
    )
    (net (code "77") (name "unconnected-(PCB1-GPIO9-PadP$21)") (class "Default")
      (node (ref "PCB1") (pin "P$21") (pinfunction "GPIO9_P$21") (pintype "bidirectional"))
    )
    (net (code "78") (name "unconnected-(PCB1-GPIO10-PadP$19)") (class "Default")
      (node (ref "PCB1") (pin "P$19") (pinfunction "GPIO10_P$19") (pintype "bidirectional"))
    )
    (net (code "79") (name "unconnected-(PCB1-GPIO11-PadP$23)") (class "Default")
      (node (ref "PCB1") (pin "P$23") (pinfunction "GPIO11_P$23") (pintype "bidirectional"))
    )
    (net (code "80") (name "unconnected-(PCB1-GPIO12-PadP$32)") (class "Default")
      (node (ref "PCB1") (pin "P$32") (pinfunction "GPIO12_P$32") (pintype "bidirectional"))
    )
    (net (code "81") (name "unconnected-(PCB1-GPIO13-PadP$33)") (class "Default")
      (node (ref "PCB1") (pin "P$33") (pinfunction "GPIO13_P$33") (pintype "bidirectional"))
    )
    (net (code "82") (name "unconnected-(PCB1-GPIO14-PadP$8)") (class "Default")
      (node (ref "PCB1") (pin "P$8") (pinfunction "GPIO14_P$8") (pintype "bidirectional"))
    )
    (net (code "83") (name "unconnected-(PCB1-GPIO15-PadP$10)") (class "Default")
      (node (ref "PCB1") (pin "P$10") (pinfunction "GPIO15_P$10") (pintype "bidirectional"))
    )
    (net (code "84") (name "unconnected-(PCB1-GPIO16-PadP$36)") (class "Default")
      (node (ref "PCB1") (pin "P$36") (pinfunction "GPIO16_P$36") (pintype "bidirectional"))
    )
    (net (code "85") (name "unconnected-(PCB1-GPIO17-PadP$11)") (class "Default")
      (node (ref "PCB1") (pin "P$11") (pinfunction "GPIO17_P$11") (pintype "bidirectional"))
    )
    (net (code "86") (name "unconnected-(PCB1-GPIO18-PadP$12)") (class "Default")
      (node (ref "PCB1") (pin "P$12") (pinfunction "GPIO18_P$12") (pintype "bidirectional"))
    )
    (net (code "87") (name "unconnected-(PCB1-GPIO19-PadP$35)") (class "Default")
      (node (ref "PCB1") (pin "P$35") (pinfunction "GPIO19_P$35") (pintype "bidirectional"))
    )
    (net (code "88") (name "unconnected-(PCB1-GPIO20-PadP$38)") (class "Default")
      (node (ref "PCB1") (pin "P$38") (pinfunction "GPIO20_P$38") (pintype "bidirectional"))
    )
    (net (code "89") (name "unconnected-(PCB1-GPIO21-PadP$40)") (class "Default")
      (node (ref "PCB1") (pin "P$40") (pinfunction "GPIO21_P$40") (pintype "bidirectional"))
    )
    (net (code "90") (name "unconnected-(PCB1-GPIO22-PadP$15)") (class "Default")
      (node (ref "PCB1") (pin "P$15") (pinfunction "GPIO22_P$15") (pintype "bidirectional"))
    )
    (net (code "91") (name "unconnected-(PCB1-GPIO23-PadP$16)") (class "Default")
      (node (ref "PCB1") (pin "P$16") (pinfunction "GPIO23_P$16") (pintype "bidirectional"))
    )
    (net (code "92") (name "unconnected-(PCB1-GPIO24-PadP$18)") (class "Default")
      (node (ref "PCB1") (pin "P$18") (pinfunction "GPIO24_P$18") (pintype "bidirectional"))
    )
    (net (code "93") (name "unconnected-(PCB1-GPIO25-PadP$22)") (class "Default")
      (node (ref "PCB1") (pin "P$22") (pinfunction "GPIO25_P$22") (pintype "bidirectional"))
    )
    (net (code "94") (name "unconnected-(PCB1-GPIO26-PadP$37)") (class "Default")
      (node (ref "PCB1") (pin "P$37") (pinfunction "GPIO26_P$37") (pintype "bidirectional"))
    )
    (net (code "95") (name "unconnected-(PCB1-GPIO27-PadP$13)") (class "Default")
      (node (ref "PCB1") (pin "P$13") (pinfunction "GPIO27_P$13") (pintype "bidirectional"))
    )
    (net (code "96") (name "unconnected-(PCB1-ID_SC*-PadP$28)") (class "Default")
      (node (ref "PCB1") (pin "P$28") (pinfunction "ID_SC*_P$28") (pintype "bidirectional"))
    )
    (net (code "97") (name "unconnected-(PCB1-ID_SD*-PadP$27)") (class "Default")
      (node (ref "PCB1") (pin "P$27") (pinfunction "ID_SD*_P$27") (pintype "bidirectional"))
    )
    (net (code "98") (name "unconnected-(PCB1-RUN_1-PadP$41)") (class "Default")
      (node (ref "PCB1") (pin "P$41") (pinfunction "RUN_1_P$41") (pintype "bidirectional"))
    )
    (net (code "99") (name "unconnected-(PCB1-RUN_2-PadP$42)") (class "Default")
      (node (ref "PCB1") (pin "P$42") (pinfunction "RUN_2_P$42") (pintype "bidirectional"))
    )
    (net (code "100") (name "unconnected-(X2A-KL-Pad1)") (class "Default")
      (node (ref "X2") (pin "1") (pinfunction "KL_1") (pintype "passive"))
    )
    (net (code "101") (name "unconnected-(X2B-KL-Pad10)") (class "Default")
      (node (ref "X2") (pin "10") (pinfunction "KL_10") (pintype "passive"))
    )
    (net (code "102") (name "unconnected-(X2C-KL-Pad11)") (class "Default")
      (node (ref "X2") (pin "11") (pinfunction "KL_11") (pintype "passive"))
    )
    (net (code "103") (name "unconnected-(X2D-KL-Pad12)") (class "Default")
      (node (ref "X2") (pin "12") (pinfunction "KL_12") (pintype "passive"))
    )
    (net (code "104") (name "unconnected-(X2E-KL-Pad13)") (class "Default")
      (node (ref "X2") (pin "13") (pinfunction "KL_13") (pintype "passive"))
    )
    (net (code "105") (name "unconnected-(X2F-KL-Pad14)") (class "Default")
      (node (ref "X2") (pin "14") (pinfunction "KL_14") (pintype "passive"))
    )
    (net (code "106") (name "unconnected-(X2G-KL-Pad15)") (class "Default")
      (node (ref "X2") (pin "15") (pinfunction "KL_15") (pintype "passive"))
    )
    (net (code "107") (name "unconnected-(X2H-KL-Pad16)") (class "Default")
      (node (ref "X2") (pin "16") (pinfunction "KL_16") (pintype "passive"))
    )
    (net (code "108") (name "unconnected-(X2I-KL-Pad17)") (class "Default")
      (node (ref "X2") (pin "17") (pinfunction "KL_17") (pintype "passive"))
    )
    (net (code "109") (name "unconnected-(X2J-KL-Pad18)") (class "Default")
      (node (ref "X2") (pin "18") (pinfunction "KL_18") (pintype "passive"))
    )
    (net (code "110") (name "unconnected-(X2K-KL-Pad19)") (class "Default")
      (node (ref "X2") (pin "19") (pinfunction "KL_19") (pintype "passive"))
    )
    (net (code "111") (name "unconnected-(X2L-KL-Pad2)") (class "Default")
      (node (ref "X2") (pin "2") (pinfunction "KL_2") (pintype "passive"))
    )
    (net (code "112") (name "unconnected-(X2M-KL-Pad20)") (class "Default")
      (node (ref "X2") (pin "20") (pinfunction "KL_20") (pintype "passive"))
    )
    (net (code "113") (name "unconnected-(X2N-KL-Pad21)") (class "Default")
      (node (ref "X2") (pin "21") (pinfunction "KL_21") (pintype "passive"))
    )
    (net (code "114") (name "unconnected-(X2O-KL-Pad22)") (class "Default")
      (node (ref "X2") (pin "22") (pinfunction "KL_22") (pintype "passive"))
    )
    (net (code "115") (name "unconnected-(X2P-KL-Pad23)") (class "Default")
      (node (ref "X2") (pin "23") (pinfunction "KL_23") (pintype "passive"))
    )
    (net (code "116") (name "unconnected-(X2Q-KL-Pad24)") (class "Default")
      (node (ref "X2") (pin "24") (pinfunction "KL_24") (pintype "passive"))
    )
    (net (code "117") (name "unconnected-(X2R-KL-Pad25)") (class "Default")
      (node (ref "X2") (pin "25") (pinfunction "KL_25") (pintype "passive"))
    )
    (net (code "118") (name "unconnected-(X2S-KL-Pad26)") (class "Default")
      (node (ref "X2") (pin "26") (pinfunction "KL_26") (pintype "passive"))
    )
    (net (code "119") (name "unconnected-(X2T-KL-Pad3)") (class "Default")
      (node (ref "X2") (pin "3") (pinfunction "KL_3") (pintype "passive"))
    )
    (net (code "120") (name "unconnected-(X2U-KL-Pad4)") (class "Default")
      (node (ref "X2") (pin "4") (pinfunction "KL_4") (pintype "passive"))
    )
    (net (code "121") (name "unconnected-(X2V-KL-Pad5)") (class "Default")
      (node (ref "X2") (pin "5") (pinfunction "KL_5") (pintype "passive"))
    )
    (net (code "122") (name "unconnected-(X2W-KL-Pad6)") (class "Default")
      (node (ref "X2") (pin "6") (pinfunction "KL_6") (pintype "passive"))
    )
    (net (code "123") (name "unconnected-(X2X-KL-Pad7)") (class "Default")
      (node (ref "X2") (pin "7") (pinfunction "KL_7") (pintype "passive"))
    )
    (net (code "124") (name "unconnected-(X2Y-KL-Pad8)") (class "Default")
      (node (ref "X2") (pin "8") (pinfunction "KL_8") (pintype "passive"))
    )
    (net (code "125") (name "unconnected-(X2Z-KL-Pad9)") (class "Default")
      (node (ref "X2") (pin "9") (pinfunction "KL_9") (pintype "passive"))
    )
    (net (code "126") (name "unconnected-(X3-PadD+)") (class "Default")
      (node (ref "X3") (pin "D+") (pinfunction "D+_D+") (pintype "bidirectional"))
    )
    (net (code "127") (name "unconnected-(X3-PadD-)") (class "Default")
      (node (ref "X3") (pin "D-") (pinfunction "D-_D-") (pintype "bidirectional"))
    )
    (net (code "128") (name "unconnected-(X3-PadID)") (class "Default")
      (node (ref "X3") (pin "ID") (pinfunction "ID_ID") (pintype "bidirectional"))
    )
  )
)
